# untitled.net
KiCad netlist of a schematic drawn in EAGLE
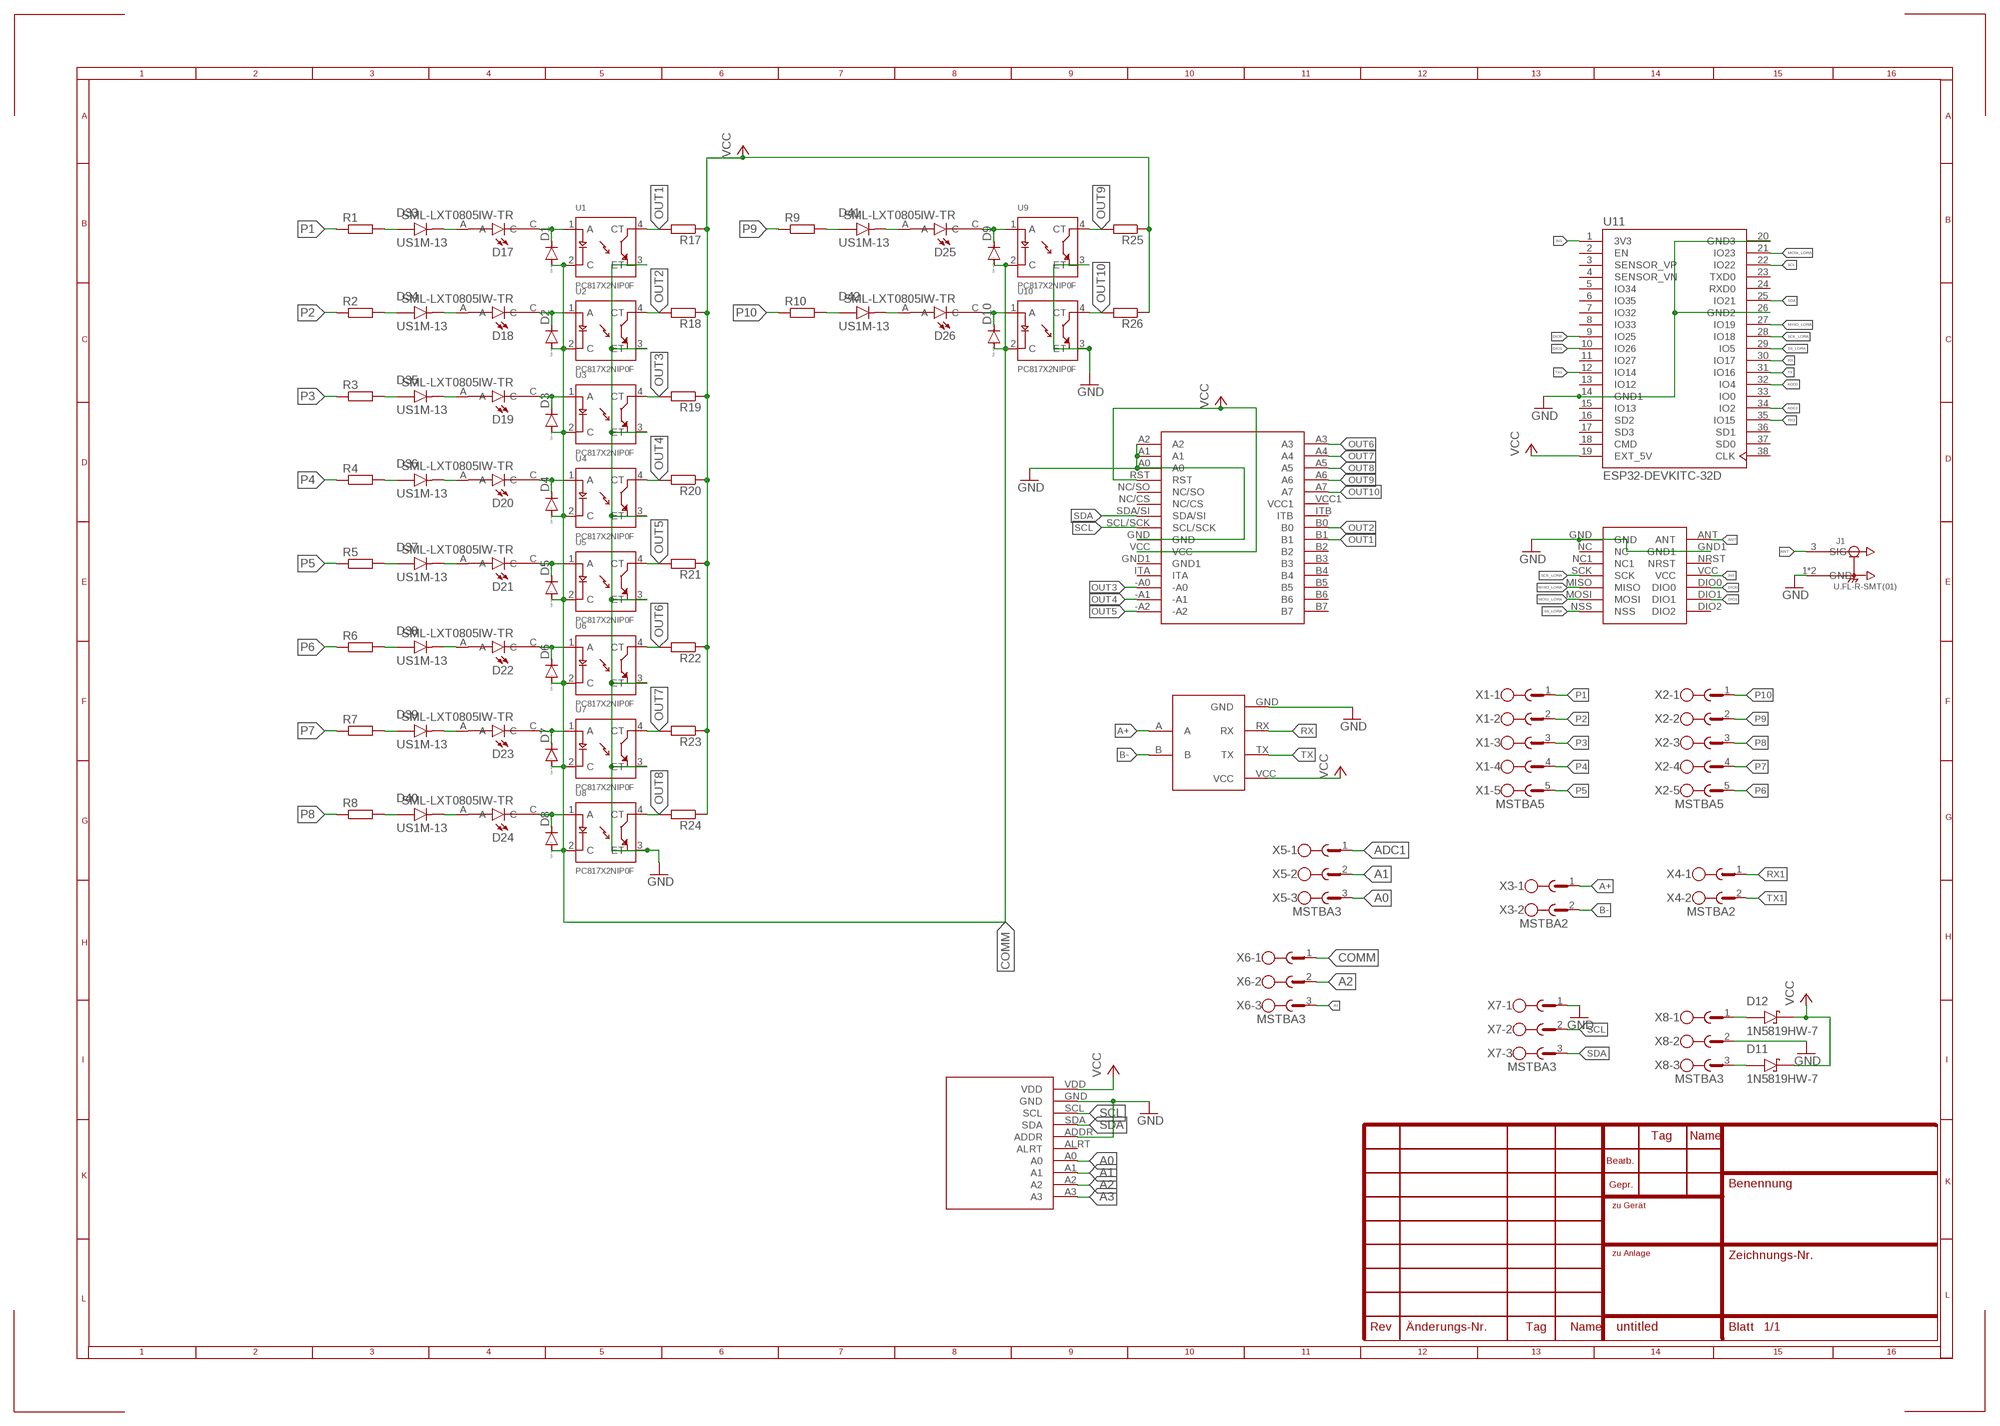
[diagram p0: schematic, sheet 1]

(export (version "E")
  (design (tool "Eeschema 10.0.6"))
  (components
    (comp (ref "ADS1")
      (value "ADS1115")
      (footprint "eagle-import:ADS1115")
      (libsource (lib "eagle-import") (part "ADS1115"))
    )
    (comp (ref "D1")
      (value "DIODE-SOD123")
      (footprint "eagle-import:SOD123")
      (libsource (lib "eagle-import") (part "DIODE-SOD123"))
    )
    (comp (ref "D2")
      (value "DIODE-SOD123")
      (footprint "eagle-import:SOD123")
      (libsource (lib "eagle-import") (part "DIODE-SOD123"))
    )
    (comp (ref "D3")
      (value "DIODE-SOD123")
      (footprint "eagle-import:SOD123")
      (libsource (lib "eagle-import") (part "DIODE-SOD123"))
    )
    (comp (ref "D4")
      (value "DIODE-SOD123")
      (footprint "eagle-import:SOD123")
      (libsource (lib "eagle-import") (part "DIODE-SOD123"))
    )
    (comp (ref "D5")
      (value "DIODE-SOD123")
      (footprint "eagle-import:SOD123")
      (libsource (lib "eagle-import") (part "DIODE-SOD123"))
    )
    (comp (ref "D6")
      (value "DIODE-SOD123")
      (footprint "eagle-import:SOD123")
      (libsource (lib "eagle-import") (part "DIODE-SOD123"))
    )
    (comp (ref "D7")
      (value "DIODE-SOD123")
      (footprint "eagle-import:SOD123")
      (libsource (lib "eagle-import") (part "DIODE-SOD123"))
    )
    (comp (ref "D8")
      (value "DIODE-SOD123")
      (footprint "eagle-import:SOD123")
      (libsource (lib "eagle-import") (part "DIODE-SOD123"))
    )
    (comp (ref "D9")
      (value "DIODE-SOD123")
      (footprint "eagle-import:SOD123")
      (libsource (lib "eagle-import") (part "DIODE-SOD123"))
    )
    (comp (ref "D10")
      (value "DIODE-SOD123")
      (footprint "eagle-import:SOD123")
      (libsource (lib "eagle-import") (part "DIODE-SOD123"))
    )
    (comp (ref "D11")
      (value "1N5819HW-7")
      (footprint "eagle-import:SOD3715X145N")
      (fields (field (name "MF") "Diodes Inc."))
      (libsource (lib "eagle-import") (part "1N5819HW-7"))
    )
    (comp (ref "D12")
      (value "1N5819HW-7")
      (footprint "eagle-import:SOD3715X145N")
      (fields (field (name "MF") "Diodes Inc."))
      (libsource (lib "eagle-import") (part "1N5819HW-7"))
    )
    (comp (ref "D17")
      (value "SML-LXT0805IW-TR")
      (footprint "eagle-import:LEDC2012X120N")
      (fields (field (name "MF") "Lumex Opto/Components"))
      (libsource (lib "eagle-import") (part "SML-LXT0805IW-TR"))
    )
    (comp (ref "D18")
      (value "SML-LXT0805IW-TR")
      (footprint "eagle-import:LEDC2012X120N")
      (fields (field (name "MF") "Lumex Opto/Components"))
      (libsource (lib "eagle-import") (part "SML-LXT0805IW-TR"))
    )
    (comp (ref "D19")
      (value "SML-LXT0805IW-TR")
      (footprint "eagle-import:LEDC2012X120N")
      (fields (field (name "MF") "Lumex Opto/Components"))
      (libsource (lib "eagle-import") (part "SML-LXT0805IW-TR"))
    )
    (comp (ref "D20")
      (value "SML-LXT0805IW-TR")
      (footprint "eagle-import:LEDC2012X120N")
      (fields (field (name "MF") "Lumex Opto/Components"))
      (libsource (lib "eagle-import") (part "SML-LXT0805IW-TR"))
    )
    (comp (ref "D21")
      (value "SML-LXT0805IW-TR")
      (footprint "eagle-import:LEDC2012X120N")
      (fields (field (name "MF") "Lumex Opto/Components"))
      (libsource (lib "eagle-import") (part "SML-LXT0805IW-TR"))
    )
    (comp (ref "D22")
      (value "SML-LXT0805IW-TR")
      (footprint "eagle-import:LEDC2012X120N")
      (fields (field (name "MF") "Lumex Opto/Components"))
      (libsource (lib "eagle-import") (part "SML-LXT0805IW-TR"))
    )
    (comp (ref "D23")
      (value "SML-LXT0805IW-TR")
      (footprint "eagle-import:LEDC2012X120N")
      (fields (field (name "MF") "Lumex Opto/Components"))
      (libsource (lib "eagle-import") (part "SML-LXT0805IW-TR"))
    )
    (comp (ref "D24")
      (value "SML-LXT0805IW-TR")
      (footprint "eagle-import:LEDC2012X120N")
      (fields (field (name "MF") "Lumex Opto/Components"))
      (libsource (lib "eagle-import") (part "SML-LXT0805IW-TR"))
    )
    (comp (ref "D25")
      (value "SML-LXT0805IW-TR")
      (footprint "eagle-import:LEDC2012X120N")
      (fields (field (name "MF") "Lumex Opto/Components"))
      (libsource (lib "eagle-import") (part "SML-LXT0805IW-TR"))
    )
    (comp (ref "D26")
      (value "SML-LXT0805IW-TR")
      (footprint "eagle-import:LEDC2012X120N")
      (fields (field (name "MF") "Lumex Opto/Components"))
      (libsource (lib "eagle-import") (part "SML-LXT0805IW-TR"))
    )
    (comp (ref "D33")
      (value "US1M-13")
      (footprint "eagle-import:DIOM5226X240N")
      (fields (field (name "MF") "Diodes Incorporated"))
      (libsource (lib "eagle-import") (part "US1M-13"))
    )
    (comp (ref "D34")
      (value "US1M-13")
      (footprint "eagle-import:DIOM5226X240N")
      (fields (field (name "MF") "Diodes Incorporated"))
      (libsource (lib "eagle-import") (part "US1M-13"))
    )
    (comp (ref "D35")
      (value "US1M-13")
      (footprint "eagle-import:DIOM5226X240N")
      (fields (field (name "MF") "Diodes Incorporated"))
      (libsource (lib "eagle-import") (part "US1M-13"))
    )
    (comp (ref "D36")
      (value "US1M-13")
      (footprint "eagle-import:DIOM5226X240N")
      (fields (field (name "MF") "Diodes Incorporated"))
      (libsource (lib "eagle-import") (part "US1M-13"))
    )
    (comp (ref "D37")
      (value "US1M-13")
      (footprint "eagle-import:DIOM5226X240N")
      (fields (field (name "MF") "Diodes Incorporated"))
      (libsource (lib "eagle-import") (part "US1M-13"))
    )
    (comp (ref "D38")
      (value "US1M-13")
      (footprint "eagle-import:DIOM5226X240N")
      (fields (field (name "MF") "Diodes Incorporated"))
      (libsource (lib "eagle-import") (part "US1M-13"))
    )
    (comp (ref "D39")
      (value "US1M-13")
      (footprint "eagle-import:DIOM5226X240N")
      (fields (field (name "MF") "Diodes Incorporated"))
      (libsource (lib "eagle-import") (part "US1M-13"))
    )
    (comp (ref "D40")
      (value "US1M-13")
      (footprint "eagle-import:DIOM5226X240N")
      (fields (field (name "MF") "Diodes Incorporated"))
      (libsource (lib "eagle-import") (part "US1M-13"))
    )
    (comp (ref "D41")
      (value "US1M-13")
      (footprint "eagle-import:DIOM5226X240N")
      (fields (field (name "MF") "Diodes Incorporated"))
      (libsource (lib "eagle-import") (part "US1M-13"))
    )
    (comp (ref "D42")
      (value "US1M-13")
      (footprint "eagle-import:DIOM5226X240N")
      (fields (field (name "MF") "Diodes Incorporated"))
      (libsource (lib "eagle-import") (part "US1M-13"))
    )
    (comp (ref "J1")
      (value "U.FL-R-SMT(01)")
      (footprint "eagle-import:HRS_U.FL-R-SMT(01)")
      (fields (field (name "MF") "Hirose"))
      (libsource (lib "eagle-import") (part "U.FL-R-SMT(01)"))
    )
    (comp (ref "LORA-NICERF-V1")
      (value "LORA-NICERF-V2")
      (footprint "eagle-import:LORA-NICERF-V2")
      (libsource (lib "eagle-import") (part "LORA-NICERF-V2"))
    )
    (comp (ref "MCP1")
      (value "MCP23017")
      (footprint "eagle-import:MCP23017")
      (libsource (lib "eagle-import") (part "MCP23017"))
    )
    (comp (ref "R1")
      (value "R-EU_0414/15")
      (footprint "eagle-import:0414_15")
      (libsource (lib "eagle-import") (part "R-EU_0414/15"))
    )
    (comp (ref "R2")
      (value "R-EU_0414/15")
      (footprint "eagle-import:0414_15")
      (libsource (lib "eagle-import") (part "R-EU_0414/15"))
    )
    (comp (ref "R3")
      (value "R-EU_0414/15")
      (footprint "eagle-import:0414_15")
      (libsource (lib "eagle-import") (part "R-EU_0414/15"))
    )
    (comp (ref "R4")
      (value "R-EU_0414/15")
      (footprint "eagle-import:0414_15")
      (libsource (lib "eagle-import") (part "R-EU_0414/15"))
    )
    (comp (ref "R5")
      (value "R-EU_0414/15")
      (footprint "eagle-import:0414_15")
      (libsource (lib "eagle-import") (part "R-EU_0414/15"))
    )
    (comp (ref "R6")
      (value "R-EU_0414/15")
      (footprint "eagle-import:0414_15")
      (libsource (lib "eagle-import") (part "R-EU_0414/15"))
    )
    (comp (ref "R7")
      (value "R-EU_0414/15")
      (footprint "eagle-import:0414_15")
      (libsource (lib "eagle-import") (part "R-EU_0414/15"))
    )
    (comp (ref "R8")
      (value "R-EU_0414/15")
      (footprint "eagle-import:0414_15")
      (libsource (lib "eagle-import") (part "R-EU_0414/15"))
    )
    (comp (ref "R9")
      (value "R-EU_0414/15")
      (footprint "eagle-import:0414_15")
      (libsource (lib "eagle-import") (part "R-EU_0414/15"))
    )
    (comp (ref "R10")
      (value "R-EU_0414/15")
      (footprint "eagle-import:0414_15")
      (libsource (lib "eagle-import") (part "R-EU_0414/15"))
    )
    (comp (ref "R17")
      (value "R-EU_R0805")
      (footprint "eagle-import:R0805")
      (libsource (lib "eagle-import") (part "R-EU_R0805"))
    )
    (comp (ref "R18")
      (value "R-EU_R0805")
      (footprint "eagle-import:R0805")
      (libsource (lib "eagle-import") (part "R-EU_R0805"))
    )
    (comp (ref "R19")
      (value "R-EU_R0805")
      (footprint "eagle-import:R0805")
      (libsource (lib "eagle-import") (part "R-EU_R0805"))
    )
    (comp (ref "R20")
      (value "R-EU_R0805")
      (footprint "eagle-import:R0805")
      (libsource (lib "eagle-import") (part "R-EU_R0805"))
    )
    (comp (ref "R21")
      (value "R-EU_R0805")
      (footprint "eagle-import:R0805")
      (libsource (lib "eagle-import") (part "R-EU_R0805"))
    )
    (comp (ref "R22")
      (value "R-EU_R0805")
      (footprint "eagle-import:R0805")
      (libsource (lib "eagle-import") (part "R-EU_R0805"))
    )
    (comp (ref "R23")
      (value "R-EU_R0805")
      (footprint "eagle-import:R0805")
      (libsource (lib "eagle-import") (part "R-EU_R0805"))
    )
    (comp (ref "R24")
      (value "R-EU_R0805")
      (footprint "eagle-import:R0805")
      (libsource (lib "eagle-import") (part "R-EU_R0805"))
    )
    (comp (ref "R25")
      (value "R-EU_R0805")
      (footprint "eagle-import:R0805")
      (libsource (lib "eagle-import") (part "R-EU_R0805"))
    )
    (comp (ref "R26")
      (value "R-EU_R0805")
      (footprint "eagle-import:R0805")
      (libsource (lib "eagle-import") (part "R-EU_R0805"))
    )
    (comp (ref "TTL-RS1")
      (value "TTL-RS485")
      (footprint "eagle-import:TTL-RS485")
      (libsource (lib "eagle-import") (part "TTL-RS485"))
    )
    (comp (ref "U1")
      (value "PC817X2NIP0F")
      (footprint "eagle-import:SOT254P975X400-4N")
      (fields (field (name "MF") "Sharp Microelectronics"))
      (libsource (lib "eagle-import") (part "PC817X2NIP0F"))
    )
    (comp (ref "U2")
      (value "PC817X2NIP0F")
      (footprint "eagle-import:SOT254P975X400-4N")
      (fields (field (name "MF") "Sharp Microelectronics"))
      (libsource (lib "eagle-import") (part "PC817X2NIP0F"))
    )
    (comp (ref "U3")
      (value "PC817X2NIP0F")
      (footprint "eagle-import:SOT254P975X400-4N")
      (fields (field (name "MF") "Sharp Microelectronics"))
      (libsource (lib "eagle-import") (part "PC817X2NIP0F"))
    )
    (comp (ref "U4")
      (value "PC817X2NIP0F")
      (footprint "eagle-import:SOT254P975X400-4N")
      (fields (field (name "MF") "Sharp Microelectronics"))
      (libsource (lib "eagle-import") (part "PC817X2NIP0F"))
    )
    (comp (ref "U5")
      (value "PC817X2NIP0F")
      (footprint "eagle-import:SOT254P975X400-4N")
      (fields (field (name "MF") "Sharp Microelectronics"))
      (libsource (lib "eagle-import") (part "PC817X2NIP0F"))
    )
    (comp (ref "U6")
      (value "PC817X2NIP0F")
      (footprint "eagle-import:SOT254P975X400-4N")
      (fields (field (name "MF") "Sharp Microelectronics"))
      (libsource (lib "eagle-import") (part "PC817X2NIP0F"))
    )
    (comp (ref "U7")
      (value "PC817X2NIP0F")
      (footprint "eagle-import:SOT254P975X400-4N")
      (fields (field (name "MF") "Sharp Microelectronics"))
      (libsource (lib "eagle-import") (part "PC817X2NIP0F"))
    )
    (comp (ref "U8")
      (value "PC817X2NIP0F")
      (footprint "eagle-import:SOT254P975X400-4N")
      (fields (field (name "MF") "Sharp Microelectronics"))
      (libsource (lib "eagle-import") (part "PC817X2NIP0F"))
    )
    (comp (ref "U9")
      (value "PC817X2NIP0F")
      (footprint "eagle-import:SOT254P975X400-4N")
      (fields (field (name "MF") "Sharp Microelectronics"))
      (libsource (lib "eagle-import") (part "PC817X2NIP0F"))
    )
    (comp (ref "U10")
      (value "PC817X2NIP0F")
      (footprint "eagle-import:SOT254P975X400-4N")
      (fields (field (name "MF") "Sharp Microelectronics"))
      (libsource (lib "eagle-import") (part "PC817X2NIP0F"))
    )
    (comp (ref "U11")
      (value "ESP32-DEVKITC-32D")
      (footprint "eagle-import:MODULE_ESP32-DEVKITC-32D")
      (fields (field (name "MF") "Espressif Systems"))
      (libsource (lib "eagle-import") (part "ESP32-DEVKITC-32D"))
    )
    (comp (ref "X1")
      (value "MSTBA5")
      (footprint "eagle-import:MSTBA5")
      (fields (field (name "MPN") "1757271"))
      (libsource (lib "eagle-import") (part "MSTBA5"))
    )
    (comp (ref "X2")
      (value "MSTBA5")
      (footprint "eagle-import:MSTBA5")
      (fields (field (name "MPN") "1757271"))
      (libsource (lib "eagle-import") (part "MSTBA5"))
    )
    (comp (ref "X3")
      (value "MSTBA2")
      (footprint "eagle-import:MSTBA2")
      (fields (field (name "MF") "FARNELL") (field (name "MPN") "1757242"))
      (libsource (lib "eagle-import") (part "MSTBA2"))
    )
    (comp (ref "X4")
      (value "MSTBA2")
      (footprint "eagle-import:MSTBA2")
      (fields (field (name "MF") "FARNELL") (field (name "MPN") "1757242"))
      (libsource (lib "eagle-import") (part "MSTBA2"))
    )
    (comp (ref "X5")
      (value "MSTBA3")
      (footprint "eagle-import:MSTBA3")
      (fields (field (name "MF") "FARNELL") (field (name "MPN") "1757255"))
      (libsource (lib "eagle-import") (part "MSTBA3"))
    )
    (comp (ref "X6")
      (value "MSTBA3")
      (footprint "eagle-import:MSTBA3")
      (fields (field (name "MF") "FARNELL") (field (name "MPN") "1757255"))
      (libsource (lib "eagle-import") (part "MSTBA3"))
    )
    (comp (ref "X7")
      (value "MSTBA3")
      (footprint "eagle-import:MSTBA3")
      (fields (field (name "MF") "FARNELL") (field (name "MPN") "1757255"))
      (libsource (lib "eagle-import") (part "MSTBA3"))
    )
    (comp (ref "X8")
      (value "MSTBA3")
      (footprint "eagle-import:MSTBA3")
      (fields (field (name "MF") "FARNELL") (field (name "MPN") "1757255"))
      (libsource (lib "eagle-import") (part "MSTBA3"))
    )
  )
  (nets
    (net (code "1") (name "3V3") (class "Default")
      (node (ref "LORA-NICERF-V1") (pin "VCC") (pinfunction "VCC_VCC") (pintype "bidirectional"))
      (node (ref "U11") (pin "1") (pinfunction "3V3_1") (pintype "power_in"))
    )
    (net (code "2") (name "A+") (class "Default")
      (node (ref "TTL-RS1") (pin "A") (pinfunction "A_A") (pintype "bidirectional"))
      (node (ref "X3") (pin "1") (pinfunction "1_1") (pintype "passive"))
    )
    (net (code "3") (name "A0") (class "Default")
      (node (ref "ADS1") (pin "A0") (pinfunction "A0_A0") (pintype "bidirectional"))
      (node (ref "X5") (pin "3") (pinfunction "1_3") (pintype "passive"))
    )
    (net (code "4") (name "A1") (class "Default")
      (node (ref "ADS1") (pin "A1") (pinfunction "A1_A1") (pintype "bidirectional"))
      (node (ref "X5") (pin "2") (pinfunction "1_2") (pintype "passive"))
    )
    (net (code "5") (name "A2") (class "Default")
      (node (ref "ADS1") (pin "A2") (pinfunction "A2_A2") (pintype "bidirectional"))
      (node (ref "X6") (pin "2") (pinfunction "1_2") (pintype "passive"))
    )
    (net (code "6") (name "A3") (class "Default")
      (node (ref "ADS1") (pin "A3") (pinfunction "A3_A3") (pintype "bidirectional"))
      (node (ref "X6") (pin "3") (pinfunction "1_3") (pintype "passive"))
    )
    (net (code "7") (name "ADC0") (class "Default")
      (node (ref "U11") (pin "32") (pinfunction "IO4_32") (pintype "bidirectional"))
    )
    (net (code "8") (name "ADC1") (class "Default")
      (node (ref "U11") (pin "34") (pinfunction "IO2_34") (pintype "bidirectional"))
      (node (ref "X5") (pin "1") (pinfunction "1_1") (pintype "passive"))
    )
    (net (code "9") (name "ANT") (class "Default")
      (node (ref "J1") (pin "3") (pinfunction "SIG_3") (pintype "passive"))
      (node (ref "LORA-NICERF-V1") (pin "ANT") (pinfunction "ANT_ANT") (pintype "bidirectional"))
    )
    (net (code "10") (name "B-") (class "Default")
      (node (ref "TTL-RS1") (pin "B") (pinfunction "B_B") (pintype "bidirectional"))
      (node (ref "X3") (pin "2") (pinfunction "1_2") (pintype "passive"))
    )
    (net (code "11") (name "COMM") (class "Default")
      (node (ref "D1") (pin "A") (pinfunction "A_A") (pintype "passive"))
      (node (ref "D10") (pin "A") (pinfunction "A_A") (pintype "passive"))
      (node (ref "D2") (pin "A") (pinfunction "A_A") (pintype "passive"))
      (node (ref "D3") (pin "A") (pinfunction "A_A") (pintype "passive"))
      (node (ref "D4") (pin "A") (pinfunction "A_A") (pintype "passive"))
      (node (ref "D5") (pin "A") (pinfunction "A_A") (pintype "passive"))
      (node (ref "D6") (pin "A") (pinfunction "A_A") (pintype "passive"))
      (node (ref "D7") (pin "A") (pinfunction "A_A") (pintype "passive"))
      (node (ref "D8") (pin "A") (pinfunction "A_A") (pintype "passive"))
      (node (ref "D9") (pin "A") (pinfunction "A_A") (pintype "passive"))
      (node (ref "U1") (pin "2") (pinfunction "C_2") (pintype "passive"))
      (node (ref "U10") (pin "2") (pinfunction "C_2") (pintype "passive"))
      (node (ref "U2") (pin "2") (pinfunction "C_2") (pintype "passive"))
      (node (ref "U3") (pin "2") (pinfunction "C_2") (pintype "passive"))
      (node (ref "U4") (pin "2") (pinfunction "C_2") (pintype "passive"))
      (node (ref "U5") (pin "2") (pinfunction "C_2") (pintype "passive"))
      (node (ref "U6") (pin "2") (pinfunction "C_2") (pintype "passive"))
      (node (ref "U7") (pin "2") (pinfunction "C_2") (pintype "passive"))
      (node (ref "U8") (pin "2") (pinfunction "C_2") (pintype "passive"))
      (node (ref "U9") (pin "2") (pinfunction "C_2") (pintype "passive"))
      (node (ref "X6") (pin "1") (pinfunction "1_1") (pintype "passive"))
    )
    (net (code "12") (name "DIO0") (class "Default")
      (node (ref "LORA-NICERF-V1") (pin "DIO0") (pinfunction "DIO0_DIO0") (pintype "bidirectional"))
      (node (ref "U11") (pin "9") (pinfunction "IO25_9") (pintype "bidirectional"))
    )
    (net (code "13") (name "DIO1") (class "Default")
      (node (ref "LORA-NICERF-V1") (pin "DIO1") (pinfunction "DIO1_DIO1") (pintype "bidirectional"))
      (node (ref "U11") (pin "10") (pinfunction "IO26_10") (pintype "bidirectional"))
    )
    (net (code "14") (name "GND") (class "Default")
      (node (ref "ADS1") (pin "ADDR") (pinfunction "ADDR_ADDR") (pintype "bidirectional"))
      (node (ref "ADS1") (pin "GND") (pinfunction "GND_GND") (pintype "bidirectional"))
      (node (ref "J1") (pin "1") (pinfunction "GND_1") (pintype "passive"))
      (node (ref "J1") (pin "2") (pinfunction "GND_2") (pintype "passive"))
      (node (ref "LORA-NICERF-V1") (pin "GND") (pinfunction "GND_GND") (pintype "bidirectional"))
      (node (ref "LORA-NICERF-V1") (pin "GND1") (pinfunction "GND1_GND1") (pintype "bidirectional"))
      (node (ref "MCP1") (pin "A0") (pinfunction "A0_A0") (pintype "bidirectional"))
      (node (ref "MCP1") (pin "A1") (pinfunction "A1_A1") (pintype "bidirectional"))
      (node (ref "MCP1") (pin "A2") (pinfunction "A2_A2") (pintype "bidirectional"))
      (node (ref "MCP1") (pin "GND") (pinfunction "GND_GND") (pintype "bidirectional"))
      (node (ref "TTL-RS1") (pin "GND") (pinfunction "GND_GND") (pintype "bidirectional"))
      (node (ref "U1") (pin "3") (pinfunction "ET_3") (pintype "passive"))
      (node (ref "U10") (pin "3") (pinfunction "ET_3") (pintype "passive"))
      (node (ref "U11") (pin "14") (pinfunction "GND1_14") (pintype "power_in"))
      (node (ref "U11") (pin "20") (pinfunction "GND3_20") (pintype "power_in"))
      (node (ref "U11") (pin "26") (pinfunction "GND2_26") (pintype "power_in"))
      (node (ref "U2") (pin "3") (pinfunction "ET_3") (pintype "passive"))
      (node (ref "U3") (pin "3") (pinfunction "ET_3") (pintype "passive"))
      (node (ref "U4") (pin "3") (pinfunction "ET_3") (pintype "passive"))
      (node (ref "U5") (pin "3") (pinfunction "ET_3") (pintype "passive"))
      (node (ref "U6") (pin "3") (pinfunction "ET_3") (pintype "passive"))
      (node (ref "U7") (pin "3") (pinfunction "ET_3") (pintype "passive"))
      (node (ref "U8") (pin "3") (pinfunction "ET_3") (pintype "passive"))
      (node (ref "U9") (pin "3") (pinfunction "ET_3") (pintype "passive"))
      (node (ref "X7") (pin "1") (pinfunction "1_1") (pintype "passive"))
      (node (ref "X8") (pin "2") (pinfunction "1_2") (pintype "passive"))
    )
    (net (code "15") (name "MISO_LORA") (class "Default")
      (node (ref "LORA-NICERF-V1") (pin "MISO") (pinfunction "MISO_MISO") (pintype "bidirectional"))
      (node (ref "U11") (pin "27") (pinfunction "IO19_27") (pintype "bidirectional"))
    )
    (net (code "16") (name "MOSI_LORA") (class "Default")
      (node (ref "LORA-NICERF-V1") (pin "MOSI") (pinfunction "MOSI_MOSI") (pintype "bidirectional"))
      (node (ref "U11") (pin "21") (pinfunction "IO23_21") (pintype "bidirectional"))
    )
    (net (code "17") (name "Net-(D12-PadA)") (class "Default")
      (node (ref "D12") (pin "A") (pinfunction "A_A") (pintype "passive"))
      (node (ref "X8") (pin "1") (pinfunction "1_1") (pintype "passive"))
    )
    (net (code "18") (name "Net-(D33-K)") (class "Default")
      (node (ref "D17") (pin "A") (pinfunction "A_A") (pintype "passive"))
      (node (ref "D33") (pin "C") (pinfunction "K_C") (pintype "passive"))
    )
    (net (code "19") (name "Net-(D33-PadA)") (class "Default")
      (node (ref "D33") (pin "A") (pinfunction "A_A") (pintype "passive"))
      (node (ref "R1") (pin "2") (pinfunction "2_2") (pintype "passive"))
    )
    (net (code "20") (name "Net-(D34-K)") (class "Default")
      (node (ref "D18") (pin "A") (pinfunction "A_A") (pintype "passive"))
      (node (ref "D34") (pin "C") (pinfunction "K_C") (pintype "passive"))
    )
    (net (code "21") (name "Net-(D34-PadA)") (class "Default")
      (node (ref "D34") (pin "A") (pinfunction "A_A") (pintype "passive"))
      (node (ref "R2") (pin "2") (pinfunction "2_2") (pintype "passive"))
    )
    (net (code "22") (name "Net-(D35-K)") (class "Default")
      (node (ref "D19") (pin "A") (pinfunction "A_A") (pintype "passive"))
      (node (ref "D35") (pin "C") (pinfunction "K_C") (pintype "passive"))
    )
    (net (code "23") (name "Net-(D35-PadA)") (class "Default")
      (node (ref "D35") (pin "A") (pinfunction "A_A") (pintype "passive"))
      (node (ref "R3") (pin "2") (pinfunction "2_2") (pintype "passive"))
    )
    (net (code "24") (name "Net-(D36-K)") (class "Default")
      (node (ref "D20") (pin "A") (pinfunction "A_A") (pintype "passive"))
      (node (ref "D36") (pin "C") (pinfunction "K_C") (pintype "passive"))
    )
    (net (code "25") (name "Net-(D36-PadA)") (class "Default")
      (node (ref "D36") (pin "A") (pinfunction "A_A") (pintype "passive"))
      (node (ref "R4") (pin "2") (pinfunction "2_2") (pintype "passive"))
    )
    (net (code "26") (name "Net-(D37-K)") (class "Default")
      (node (ref "D21") (pin "A") (pinfunction "A_A") (pintype "passive"))
      (node (ref "D37") (pin "C") (pinfunction "K_C") (pintype "passive"))
    )
    (net (code "27") (name "Net-(D37-PadA)") (class "Default")
      (node (ref "D37") (pin "A") (pinfunction "A_A") (pintype "passive"))
      (node (ref "R5") (pin "2") (pinfunction "2_2") (pintype "passive"))
    )
    (net (code "28") (name "Net-(D38-K)") (class "Default")
      (node (ref "D22") (pin "A") (pinfunction "A_A") (pintype "passive"))
      (node (ref "D38") (pin "C") (pinfunction "K_C") (pintype "passive"))
    )
    (net (code "29") (name "Net-(D38-PadA)") (class "Default")
      (node (ref "D38") (pin "A") (pinfunction "A_A") (pintype "passive"))
      (node (ref "R6") (pin "2") (pinfunction "2_2") (pintype "passive"))
    )
    (net (code "30") (name "Net-(D39-K)") (class "Default")
      (node (ref "D23") (pin "A") (pinfunction "A_A") (pintype "passive"))
      (node (ref "D39") (pin "C") (pinfunction "K_C") (pintype "passive"))
    )
    (net (code "31") (name "Net-(D39-PadA)") (class "Default")
      (node (ref "D39") (pin "A") (pinfunction "A_A") (pintype "passive"))
      (node (ref "R7") (pin "2") (pinfunction "2_2") (pintype "passive"))
    )
    (net (code "32") (name "Net-(D40-K)") (class "Default")
      (node (ref "D24") (pin "A") (pinfunction "A_A") (pintype "passive"))
      (node (ref "D40") (pin "C") (pinfunction "K_C") (pintype "passive"))
    )
    (net (code "33") (name "Net-(D40-PadA)") (class "Default")
      (node (ref "D40") (pin "A") (pinfunction "A_A") (pintype "passive"))
      (node (ref "R8") (pin "2") (pinfunction "2_2") (pintype "passive"))
    )
    (net (code "34") (name "Net-(D41-K)") (class "Default")
      (node (ref "D25") (pin "A") (pinfunction "A_A") (pintype "passive"))
      (node (ref "D41") (pin "C") (pinfunction "K_C") (pintype "passive"))
    )
    (net (code "35") (name "Net-(D41-PadA)") (class "Default")
      (node (ref "D41") (pin "A") (pinfunction "A_A") (pintype "passive"))
      (node (ref "R9") (pin "2") (pinfunction "2_2") (pintype "passive"))
    )
    (net (code "36") (name "Net-(D42-K)") (class "Default")
      (node (ref "D26") (pin "A") (pinfunction "A_A") (pintype "passive"))
      (node (ref "D42") (pin "C") (pinfunction "K_C") (pintype "passive"))
    )
    (net (code "37") (name "Net-(D42-PadA)") (class "Default")
      (node (ref "D42") (pin "A") (pinfunction "A_A") (pintype "passive"))
      (node (ref "R10") (pin "2") (pinfunction "2_2") (pintype "passive"))
    )
    (net (code "38") (name "Net-(U1-A)") (class "Default")
      (node (ref "D1") (pin "C") (pinfunction "C_C") (pintype "passive"))
      (node (ref "D17") (pin "C") (pinfunction "C_C") (pintype "passive"))
      (node (ref "U1") (pin "1") (pinfunction "A_1") (pintype "passive"))
    )
    (net (code "39") (name "Net-(U2-A)") (class "Default")
      (node (ref "D18") (pin "C") (pinfunction "C_C") (pintype "passive"))
      (node (ref "D2") (pin "C") (pinfunction "C_C") (pintype "passive"))
      (node (ref "U2") (pin "1") (pinfunction "A_1") (pintype "passive"))
    )
    (net (code "40") (name "Net-(U3-A)") (class "Default")
      (node (ref "D19") (pin "C") (pinfunction "C_C") (pintype "passive"))
      (node (ref "D3") (pin "C") (pinfunction "C_C") (pintype "passive"))
      (node (ref "U3") (pin "1") (pinfunction "A_1") (pintype "passive"))
    )
    (net (code "41") (name "Net-(U4-A)") (class "Default")
      (node (ref "D20") (pin "C") (pinfunction "C_C") (pintype "passive"))
      (node (ref "D4") (pin "C") (pinfunction "C_C") (pintype "passive"))
      (node (ref "U4") (pin "1") (pinfunction "A_1") (pintype "passive"))
    )
    (net (code "42") (name "Net-(U5-A)") (class "Default")
      (node (ref "D21") (pin "C") (pinfunction "C_C") (pintype "passive"))
      (node (ref "D5") (pin "C") (pinfunction "C_C") (pintype "passive"))
      (node (ref "U5") (pin "1") (pinfunction "A_1") (pintype "passive"))
    )
    (net (code "43") (name "Net-(U6-A)") (class "Default")
      (node (ref "D22") (pin "C") (pinfunction "C_C") (pintype "passive"))
      (node (ref "D6") (pin "C") (pinfunction "C_C") (pintype "passive"))
      (node (ref "U6") (pin "1") (pinfunction "A_1") (pintype "passive"))
    )
    (net (code "44") (name "Net-(U7-A)") (class "Default")
      (node (ref "D23") (pin "C") (pinfunction "C_C") (pintype "passive"))
      (node (ref "D7") (pin "C") (pinfunction "C_C") (pintype "passive"))
      (node (ref "U7") (pin "1") (pinfunction "A_1") (pintype "passive"))
    )
    (net (code "45") (name "Net-(U8-A)") (class "Default")
      (node (ref "D24") (pin "C") (pinfunction "C_C") (pintype "passive"))
      (node (ref "D8") (pin "C") (pinfunction "C_C") (pintype "passive"))
      (node (ref "U8") (pin "1") (pinfunction "A_1") (pintype "passive"))
    )
    (net (code "46") (name "Net-(U9-A)") (class "Default")
      (node (ref "D25") (pin "C") (pinfunction "C_C") (pintype "passive"))
      (node (ref "D9") (pin "C") (pinfunction "C_C") (pintype "passive"))
      (node (ref "U9") (pin "1") (pinfunction "A_1") (pintype "passive"))
    )
    (net (code "47") (name "Net-(U10-A)") (class "Default")
      (node (ref "D10") (pin "C") (pinfunction "C_C") (pintype "passive"))
      (node (ref "D26") (pin "C") (pinfunction "C_C") (pintype "passive"))
      (node (ref "U10") (pin "1") (pinfunction "A_1") (pintype "passive"))
    )
    (net (code "48") (name "Net-(X8C-1)") (class "Default")
      (node (ref "D11") (pin "A") (pinfunction "A_A") (pintype "passive"))
      (node (ref "X8") (pin "3") (pinfunction "1_3") (pintype "passive"))
    )
    (net (code "49") (name "OUT1") (class "Default")
      (node (ref "MCP1") (pin "B1") (pinfunction "B1_B1") (pintype "bidirectional"))
      (node (ref "R17") (pin "2") (pinfunction "2_2") (pintype "passive"))
      (node (ref "U1") (pin "4") (pinfunction "CT_4") (pintype "passive"))
    )
    (net (code "50") (name "OUT2") (class "Default")
      (node (ref "MCP1") (pin "B0") (pinfunction "B0_B0") (pintype "bidirectional"))
      (node (ref "R18") (pin "2") (pinfunction "2_2") (pintype "passive"))
      (node (ref "U2") (pin "4") (pinfunction "CT_4") (pintype "passive"))
    )
    (net (code "51") (name "OUT3") (class "Default")
      (node (ref "MCP1") (pin "-A0") (pinfunction "-A0_-A0") (pintype "bidirectional"))
      (node (ref "R19") (pin "2") (pinfunction "2_2") (pintype "passive"))
      (node (ref "U3") (pin "4") (pinfunction "CT_4") (pintype "passive"))
    )
    (net (code "52") (name "OUT4") (class "Default")
      (node (ref "MCP1") (pin "-A1") (pinfunction "-A1_-A1") (pintype "bidirectional"))
      (node (ref "R20") (pin "2") (pinfunction "2_2") (pintype "passive"))
      (node (ref "U4") (pin "4") (pinfunction "CT_4") (pintype "passive"))
    )
    (net (code "53") (name "OUT5") (class "Default")
      (node (ref "MCP1") (pin "-A2") (pinfunction "-A2_-A2") (pintype "bidirectional"))
      (node (ref "R21") (pin "2") (pinfunction "2_2") (pintype "passive"))
      (node (ref "U5") (pin "4") (pinfunction "CT_4") (pintype "passive"))
    )
    (net (code "54") (name "OUT6") (class "Default")
      (node (ref "MCP1") (pin "A3") (pinfunction "A3_A3") (pintype "bidirectional"))
      (node (ref "R22") (pin "2") (pinfunction "2_2") (pintype "passive"))
      (node (ref "U6") (pin "4") (pinfunction "CT_4") (pintype "passive"))
    )
    (net (code "55") (name "OUT7") (class "Default")
      (node (ref "MCP1") (pin "A4") (pinfunction "A4_A4") (pintype "bidirectional"))
      (node (ref "R23") (pin "2") (pinfunction "2_2") (pintype "passive"))
      (node (ref "U7") (pin "4") (pinfunction "CT_4") (pintype "passive"))
    )
    (net (code "56") (name "OUT8") (class "Default")
      (node (ref "MCP1") (pin "A5") (pinfunction "A5_A5") (pintype "bidirectional"))
      (node (ref "R24") (pin "2") (pinfunction "2_2") (pintype "passive"))
      (node (ref "U8") (pin "4") (pinfunction "CT_4") (pintype "passive"))
    )
    (net (code "57") (name "OUT9") (class "Default")
      (node (ref "MCP1") (pin "A6") (pinfunction "A6_A6") (pintype "bidirectional"))
      (node (ref "R25") (pin "2") (pinfunction "2_2") (pintype "passive"))
      (node (ref "U9") (pin "4") (pinfunction "CT_4") (pintype "passive"))
    )
    (net (code "58") (name "OUT10") (class "Default")
      (node (ref "MCP1") (pin "A7") (pinfunction "A7_A7") (pintype "bidirectional"))
      (node (ref "R26") (pin "2") (pinfunction "2_2") (pintype "passive"))
      (node (ref "U10") (pin "4") (pinfunction "CT_4") (pintype "passive"))
    )
    (net (code "59") (name "P1") (class "Default")
      (node (ref "R1") (pin "1") (pinfunction "1_1") (pintype "passive"))
      (node (ref "X1") (pin "1") (pinfunction "1_1") (pintype "passive"))
    )
    (net (code "60") (name "P2") (class "Default")
      (node (ref "R2") (pin "1") (pinfunction "1_1") (pintype "passive"))
      (node (ref "X1") (pin "2") (pinfunction "1_2") (pintype "passive"))
    )
    (net (code "61") (name "P3") (class "Default")
      (node (ref "R3") (pin "1") (pinfunction "1_1") (pintype "passive"))
      (node (ref "X1") (pin "3") (pinfunction "1_3") (pintype "passive"))
    )
    (net (code "62") (name "P4") (class "Default")
      (node (ref "R4") (pin "1") (pinfunction "1_1") (pintype "passive"))
      (node (ref "X1") (pin "4") (pinfunction "1_4") (pintype "passive"))
    )
    (net (code "63") (name "P5") (class "Default")
      (node (ref "R5") (pin "1") (pinfunction "1_1") (pintype "passive"))
      (node (ref "X1") (pin "5") (pinfunction "1_5") (pintype "passive"))
    )
    (net (code "64") (name "P6") (class "Default")
      (node (ref "R6") (pin "1") (pinfunction "1_1") (pintype "passive"))
      (node (ref "X2") (pin "5") (pinfunction "1_5") (pintype "passive"))
    )
    (net (code "65") (name "P7") (class "Default")
      (node (ref "R7") (pin "1") (pinfunction "1_1") (pintype "passive"))
      (node (ref "X2") (pin "4") (pinfunction "1_4") (pintype "passive"))
    )
    (net (code "66") (name "P8") (class "Default")
      (node (ref "R8") (pin "1") (pinfunction "1_1") (pintype "passive"))
      (node (ref "X2") (pin "3") (pinfunction "1_3") (pintype "passive"))
    )
    (net (code "67") (name "P9") (class "Default")
      (node (ref "R9") (pin "1") (pinfunction "1_1") (pintype "passive"))
      (node (ref "X2") (pin "2") (pinfunction "1_2") (pintype "passive"))
    )
    (net (code "68") (name "P10") (class "Default")
      (node (ref "R10") (pin "1") (pinfunction "1_1") (pintype "passive"))
      (node (ref "X2") (pin "1") (pinfunction "1_1") (pintype "passive"))
    )
    (net (code "69") (name "RX") (class "Default")
      (node (ref "TTL-RS1") (pin "RX") (pinfunction "RX_RX") (pintype "bidirectional"))
      (node (ref "U11") (pin "30") (pinfunction "IO17_30") (pintype "bidirectional"))
    )
    (net (code "70") (name "RX1") (class "Default")
      (node (ref "U11") (pin "35") (pinfunction "IO15_35") (pintype "bidirectional"))
      (node (ref "X4") (pin "1") (pinfunction "1_1") (pintype "passive"))
    )
    (net (code "71") (name "SCK_LORA") (class "Default")
      (node (ref "LORA-NICERF-V1") (pin "SCK") (pinfunction "SCK_SCK") (pintype "bidirectional"))
      (node (ref "U11") (pin "28") (pinfunction "IO18_28") (pintype "bidirectional"))
    )
    (net (code "72") (name "SCL") (class "Default")
      (node (ref "ADS1") (pin "SCL") (pinfunction "SCL_SCL") (pintype "bidirectional"))
      (node (ref "MCP1") (pin "SCL/SCK") (pinfunction "SCL/SCK_SCL/SCK") (pintype "bidirectional"))
      (node (ref "U11") (pin "22") (pinfunction "IO22_22") (pintype "bidirectional"))
      (node (ref "X7") (pin "2") (pinfunction "1_2") (pintype "passive"))
    )
    (net (code "73") (name "SDA") (class "Default")
      (node (ref "ADS1") (pin "SDA") (pinfunction "SDA_SDA") (pintype "bidirectional"))
      (node (ref "MCP1") (pin "SDA/SI") (pinfunction "SDA/SI_SDA/SI") (pintype "bidirectional"))
      (node (ref "U11") (pin "25") (pinfunction "IO21_25") (pintype "bidirectional"))
      (node (ref "X7") (pin "3") (pinfunction "1_3") (pintype "passive"))
    )
    (net (code "74") (name "SS_LORA") (class "Default")
      (node (ref "LORA-NICERF-V1") (pin "NSS") (pinfunction "NSS_NSS") (pintype "bidirectional"))
      (node (ref "U11") (pin "29") (pinfunction "IO5_29") (pintype "bidirectional"))
    )
    (net (code "75") (name "TX") (class "Default")
      (node (ref "TTL-RS1") (pin "TX") (pinfunction "TX_TX") (pintype "bidirectional"))
      (node (ref "U11") (pin "31") (pinfunction "IO16_31") (pintype "bidirectional"))
    )
    (net (code "76") (name "TX1") (class "Default")
      (node (ref "U11") (pin "12") (pinfunction "IO14_12") (pintype "bidirectional"))
      (node (ref "X4") (pin "2") (pinfunction "1_2") (pintype "passive"))
    )
    (net (code "77") (name "VCC") (class "Default")
      (node (ref "ADS1") (pin "VDD") (pinfunction "VDD_VDD") (pintype "bidirectional"))
      (node (ref "D11") (pin "C") (pinfunction "K_C") (pintype "passive"))
      (node (ref "D12") (pin "C") (pinfunction "K_C") (pintype "passive"))
      (node (ref "MCP1") (pin "RST") (pinfunction "RST_RST") (pintype "bidirectional"))
      (node (ref "MCP1") (pin "VCC") (pinfunction "VCC_VCC") (pintype "bidirectional"))
      (node (ref "R17") (pin "1") (pinfunction "1_1") (pintype "passive"))
      (node (ref "R18") (pin "1") (pinfunction "1_1") (pintype "passive"))
      (node (ref "R19") (pin "1") (pinfunction "1_1") (pintype "passive"))
      (node (ref "R20") (pin "1") (pinfunction "1_1") (pintype "passive"))
      (node (ref "R21") (pin "1") (pinfunction "1_1") (pintype "passive"))
      (node (ref "R22") (pin "1") (pinfunction "1_1") (pintype "passive"))
      (node (ref "R23") (pin "1") (pinfunction "1_1") (pintype "passive"))
      (node (ref "R24") (pin "1") (pinfunction "1_1") (pintype "passive"))
      (node (ref "R25") (pin "1") (pinfunction "1_1") (pintype "passive"))
      (node (ref "R26") (pin "1") (pinfunction "1_1") (pintype "passive"))
      (node (ref "TTL-RS1") (pin "VCC") (pinfunction "VCC_VCC") (pintype "bidirectional"))
      (node (ref "U11") (pin "19") (pinfunction "EXT_5V_19") (pintype "power_in"))
    )
    (net (code "78") (name "unconnected-(ADS1-PadALRT)") (class "Default")
      (node (ref "ADS1") (pin "ALRT") (pinfunction "ALRT_ALRT") (pintype "bidirectional"))
    )
    (net (code "79") (name "unconnected-(LORA-NICERF-V1-PadDIO2)") (class "Default")
      (node (ref "LORA-NICERF-V1") (pin "DIO2") (pinfunction "DIO2_DIO2") (pintype "bidirectional"))
    )
    (net (code "80") (name "unconnected-(LORA-NICERF-V1-PadNC)") (class "Default")
      (node (ref "LORA-NICERF-V1") (pin "NC") (pinfunction "NC_NC") (pintype "bidirectional"))
    )
    (net (code "81") (name "unconnected-(LORA-NICERF-V1-PadNC1)") (class "Default")
      (node (ref "LORA-NICERF-V1") (pin "NC1") (pinfunction "NC1_NC1") (pintype "bidirectional"))
    )
    (net (code "82") (name "unconnected-(LORA-NICERF-V1-PadNRST)") (class "Default")
      (node (ref "LORA-NICERF-V1") (pin "NRST") (pinfunction "NRST_NRST") (pintype "bidirectional"))
    )
    (net (code "83") (name "unconnected-(MCP1-PadB2)") (class "Default")
      (node (ref "MCP1") (pin "B2") (pinfunction "B2_B2") (pintype "bidirectional"))
    )
    (net (code "84") (name "unconnected-(MCP1-PadB3)") (class "Default")
      (node (ref "MCP1") (pin "B3") (pinfunction "B3_B3") (pintype "bidirectional"))
    )
    (net (code "85") (name "unconnected-(MCP1-PadB4)") (class "Default")
      (node (ref "MCP1") (pin "B4") (pinfunction "B4_B4") (pintype "bidirectional"))
    )
    (net (code "86") (name "unconnected-(MCP1-PadB5)") (class "Default")
      (node (ref "MCP1") (pin "B5") (pinfunction "B5_B5") (pintype "bidirectional"))
    )
    (net (code "87") (name "unconnected-(MCP1-PadB6)") (class "Default")
      (node (ref "MCP1") (pin "B6") (pinfunction "B6_B6") (pintype "bidirectional"))
    )
    (net (code "88") (name "unconnected-(MCP1-PadB7)") (class "Default")
      (node (ref "MCP1") (pin "B7") (pinfunction "B7_B7") (pintype "bidirectional"))
    )
    (net (code "89") (name "unconnected-(MCP1-PadGND1)") (class "Default")
      (node (ref "MCP1") (pin "GND1") (pinfunction "GND1_GND1") (pintype "bidirectional"))
    )
    (net (code "90") (name "unconnected-(MCP1-PadITA)") (class "Default")
      (node (ref "MCP1") (pin "ITA") (pinfunction "ITA_ITA") (pintype "bidirectional"))
    )
    (net (code "91") (name "unconnected-(MCP1-PadITB)") (class "Default")
      (node (ref "MCP1") (pin "ITB") (pinfunction "ITB_ITB") (pintype "bidirectional"))
    )
    (net (code "92") (name "unconnected-(MCP1-PadNC{slash}CS)") (class "Default")
      (node (ref "MCP1") (pin "NC/CS") (pinfunction "NC/CS_NC/CS") (pintype "bidirectional"))
    )
    (net (code "93") (name "unconnected-(MCP1-PadNC{slash}SO)") (class "Default")
      (node (ref "MCP1") (pin "NC/SO") (pinfunction "NC/SO_NC/SO") (pintype "bidirectional"))
    )
    (net (code "94") (name "unconnected-(MCP1-PadVCC1)") (class "Default")
      (node (ref "MCP1") (pin "VCC1") (pinfunction "VCC1_VCC1") (pintype "bidirectional"))
    )
    (net (code "95") (name "unconnected-(U11-CLK-Pad38)") (class "Default")
      (node (ref "U11") (pin "38") (pinfunction "CLK_38") (pintype "input"))
    )
    (net (code "96") (name "unconnected-(U11-CMD-Pad18)") (class "Default")
      (node (ref "U11") (pin "18") (pinfunction "CMD_18") (pintype "bidirectional"))
    )
    (net (code "97") (name "unconnected-(U11-EN-Pad2)") (class "Default")
      (node (ref "U11") (pin "2") (pinfunction "EN_2") (pintype "input"))
    )
    (net (code "98") (name "unconnected-(U11-IO0-Pad33)") (class "Default")
      (node (ref "U11") (pin "33") (pinfunction "IO0_33") (pintype "bidirectional"))
    )
    (net (code "99") (name "unconnected-(U11-IO12-Pad13)") (class "Default")
      (node (ref "U11") (pin "13") (pinfunction "IO12_13") (pintype "bidirectional"))
    )
    (net (code "100") (name "unconnected-(U11-IO13-Pad15)") (class "Default")
      (node (ref "U11") (pin "15") (pinfunction "IO13_15") (pintype "bidirectional"))
    )
    (net (code "101") (name "unconnected-(U11-IO27-Pad11)") (class "Default")
      (node (ref "U11") (pin "11") (pinfunction "IO27_11") (pintype "bidirectional"))
    )
    (net (code "102") (name "unconnected-(U11-IO32-Pad7)") (class "Default")
      (node (ref "U11") (pin "7") (pinfunction "IO32_7") (pintype "bidirectional"))
    )
    (net (code "103") (name "unconnected-(U11-IO33-Pad8)") (class "Default")
      (node (ref "U11") (pin "8") (pinfunction "IO33_8") (pintype "bidirectional"))
    )
    (net (code "104") (name "unconnected-(U11-IO34-Pad5)") (class "Default")
      (node (ref "U11") (pin "5") (pinfunction "IO34_5") (pintype "bidirectional"))
    )
    (net (code "105") (name "unconnected-(U11-IO35-Pad6)") (class "Default")
      (node (ref "U11") (pin "6") (pinfunction "IO35_6") (pintype "bidirectional"))
    )
    (net (code "106") (name "unconnected-(U11-RXD0-Pad24)") (class "Default")
      (node (ref "U11") (pin "24") (pinfunction "RXD0_24") (pintype "input"))
    )
    (net (code "107") (name "unconnected-(U11-SD0-Pad37)") (class "Default")
      (node (ref "U11") (pin "37") (pinfunction "SD0_37") (pintype "bidirectional"))
    )
    (net (code "108") (name "unconnected-(U11-SD1-Pad36)") (class "Default")
      (node (ref "U11") (pin "36") (pinfunction "SD1_36") (pintype "bidirectional"))
    )
    (net (code "109") (name "unconnected-(U11-SD2-Pad16)") (class "Default")
      (node (ref "U11") (pin "16") (pinfunction "SD2_16") (pintype "bidirectional"))
    )
    (net (code "110") (name "unconnected-(U11-SD3-Pad17)") (class "Default")
      (node (ref "U11") (pin "17") (pinfunction "SD3_17") (pintype "bidirectional"))
    )
    (net (code "111") (name "unconnected-(U11-SENSOR_VN-Pad4)") (class "Default")
      (node (ref "U11") (pin "4") (pinfunction "SENSOR_VN_4") (pintype "input"))
    )
    (net (code "112") (name "unconnected-(U11-SENSOR_VP-Pad3)") (class "Default")
      (node (ref "U11") (pin "3") (pinfunction "SENSOR_VP_3") (pintype "input"))
    )
    (net (code "113") (name "unconnected-(U11-TXD0-Pad23)") (class "Default")
      (node (ref "U11") (pin "23") (pinfunction "TXD0_23") (pintype "output"))
    )
  )
)
